# ASCII_Terminal.net
KiCad netlist of a schematic drawn in Altium Designer
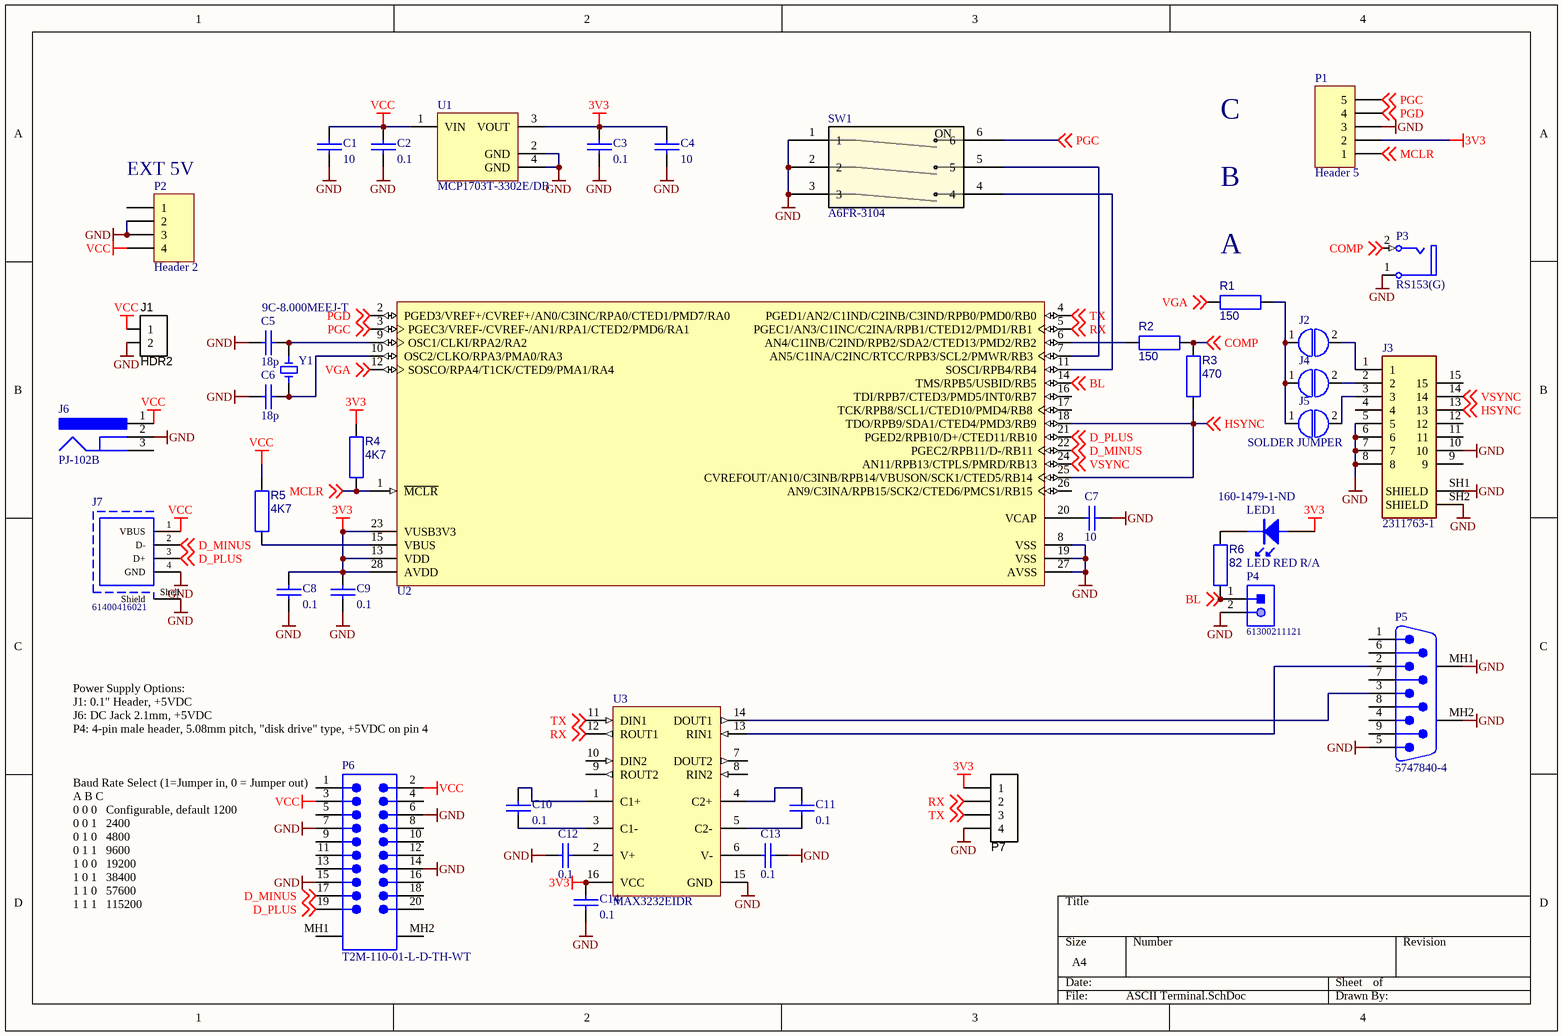
[diagram p0: ASCII Terminal.SchDoc]

(export (version "E")
  (design (tool "Eeschema 10.0.6"))
  (components
    (comp (ref "C1")
      (value "10")
      (footprint "C0805-S")
      (description "Capacitor")
      (fields (field (name "Comment") "VJ0805V475ZXQTW1BC"))
      (libsource (lib "*") (part "CAP"))
    )
    (comp (ref "C2")
      (value "0.1")
      (footprint "C0805-S")
      (description "Capacitor")
      (fields (field (name "Comment") "VJ0805V475ZXQTW1BC"))
      (libsource (lib "*") (part "CAP"))
    )
    (comp (ref "C3")
      (value "0.1")
      (footprint "C0805-S")
      (description "Capacitor")
      (fields (field (name "Comment") "VJ0805V475ZXQTW1BC"))
      (libsource (lib "*") (part "CAP"))
    )
    (comp (ref "C4")
      (value "10")
      (footprint "C0805-S")
      (description "Capacitor")
      (fields (field (name "Comment") "VJ0805V475ZXQTW1BC"))
      (libsource (lib "*") (part "CAP"))
    )
    (comp (ref "C5")
      (value "18p")
      (footprint "C0805-S")
      (description "Capacitor")
      (libsource (lib "*") (part "CAP"))
    )
    (comp (ref "C6")
      (value "18p")
      (footprint "C0805-S")
      (description "Capacitor")
      (libsource (lib "*") (part "CAP"))
    )
    (comp (ref "C7")
      (value "10")
      (footprint "C0805-S")
      (description "Capacitor")
      (fields (field (name "Comment") "VJ0805V475ZXQTW1BC"))
      (libsource (lib "*") (part "CAP"))
    )
    (comp (ref "C8")
      (value "0.1")
      (footprint "C0805-S")
      (description "Capacitor")
      (fields (field (name "Comment") "VJ0805V475ZXQTW1BC"))
      (libsource (lib "*") (part "CAP"))
    )
    (comp (ref "C9")
      (value "0.1")
      (footprint "C0805-S")
      (description "Capacitor")
      (fields (field (name "Comment") "VJ0805V475ZXQTW1BC"))
      (libsource (lib "*") (part "CAP"))
    )
    (comp (ref "C10")
      (value "0.1")
      (footprint "C0805-S")
      (description "Capacitor")
      (fields (field (name "Comment") "VJ0805V475ZXQTW1BC"))
      (libsource (lib "*") (part "CAP"))
    )
    (comp (ref "C11")
      (value "0.1")
      (footprint "C0805-S")
      (description "Capacitor")
      (fields (field (name "Comment") "VJ0805V475ZXQTW1BC"))
      (libsource (lib "*") (part "CAP"))
    )
    (comp (ref "C12")
      (value "0.1")
      (footprint "C0805-S")
      (description "Capacitor")
      (fields (field (name "Comment") "VJ0805V475ZXQTW1BC"))
      (libsource (lib "*") (part "CAP"))
    )
    (comp (ref "C13")
      (value "0.1")
      (footprint "C0805-S")
      (description "Capacitor")
      (fields (field (name "Comment") "VJ0805V475ZXQTW1BC"))
      (libsource (lib "*") (part "CAP"))
    )
    (comp (ref "C14")
      (value "0.1")
      (footprint "C0805-S")
      (description "Capacitor")
      (fields (field (name "Comment") "VJ0805V475ZXQTW1BC"))
      (libsource (lib "*") (part "CAP"))
    )
    (comp (ref "J1")
      (value "HDR2")
      (footprint "HDR1X2 - KK")
      (description "Header, 2-pin")
      (libsource (lib "PBL - Connectors") (part "Header2P"))
    )
    (comp (ref "J2")
      (value "SOLDER JUMPER")
      (footprint "SOLDER JUMPER")
      (libsource (lib "Kanitti") (part "SOLDER JUMPER"))
    )
    (comp (ref "J3")
      (value "2311763-1")
      (footprint "SnapEDApcb:TE_1-1734530-1")
      (description "15 Position D-Sub, High Density Receptacle, Female Sockets Connector")
      (fields (field (name "MP") "1-1734530-1") (field (name "MF") "TE Connectivity"))
      (libsource (lib "SnapEDAsch") (part "2311763-2"))
    )
    (comp (ref "J4")
      (value "SOLDER JUMPER")
      (footprint "SOLDER JUMPER")
      (libsource (lib "Kanitti") (part "SOLDER JUMPER"))
    )
    (comp (ref "J5")
      (value "SOLDER JUMPER")
      (footprint "SOLDER JUMPER")
      (libsource (lib "Kanitti") (part "SOLDER JUMPER"))
    )
    (comp (ref "J6")
      (value "PJ-102B")
      (footprint "CUI-PJ-102B_V")
      (fields (field (name "MANUFACTURER") "CUIInc."))
      (libsource (lib "Altium Content Vault") (part "JACK-2CD3-RN"))
    )
    (comp (ref "J7")
      (value "61400416021")
      (footprint "61400416021")
      (description "USB 2.0 Type A Receptacle WR-COM, Horizontal, THT")
      (fields (field (name "MANUFACTURER") "Wurth Elektronik") (field (name "PUBLISHER") "WurthElektronik"))
      (libsource (lib "Altium Content Vault") (part "WE-USB-4-1SHLD"))
    )
    (comp (ref "LED1")
      (value "LED RED R/A")
      (footprint "LTST-S270")
      (fields (field (name "SUPPLIER PART NUMBER 1") "160-1479-1-ND"))
      (libsource (lib "Kanitti") (part "LED_SIDE_1_6_1_15"))
    )
    (comp (ref "P1")
      (value "Header 5")
      (footprint "HDR1X5")
      (description "Header, 5-Pin")
      (fields (field (name "PUBLISHER") "Altium Limited"))
      (libsource (lib "Miscellaneous Connectors") (part "Header 5"))
    )
    (comp (ref "P2")
      (value "Header 2")
      (footprint "1745521")
      (description "Header, 4-Pin")
      (fields (field (name "PUBLISHER") "Altium Limited"))
      (libsource (lib "Kanitti") (part "Header 4"))
    )
    (comp (ref "P3")
      (value "RS153(G)")
      (footprint "RCAJ-01X")
      (description "RCA Phono Jack, Right Angle, Thru-Hole, Snap-In")
      (fields (field (name "PUBLISHER") "Altium Limited"))
      (libsource (lib "TRA1404(DIFT2)") (part "RCA"))
    )
    (comp (ref "P4")
      (value "61300211121")
      (footprint "61300211121")
      (description "THT Vertical Pin Header WR-PHD, Pitch 2.54 mm, Single Row, 2 pins")
      (fields (field (name "MANUFACTURER") "Wurth Elektronik") (field (name "PUBLISHER") "WurthElektronik"))
      (libsource (lib "Altium Content Vault") (part "WE-CN-1P-M-R2"))
    )
    (comp (ref "P5")
      (value "5747840-4")
      (footprint "TECO-5747840-4_V")
      (fields (field (name "MANUFACTURER") "TE Connectivity"))
      (libsource (lib "Altium Content Vault") (part "CN-2S-2M-D9"))
    )
    (comp (ref "P6")
      (value "T2M-110-01-L-D-TH-WT")
      (footprint "SMTC-T2M-110-01-X-D-TH-WT")
      (fields (field (name "MANUFACTURER") "Samtec"))
      (libsource (lib "Altium Content Vault") (part "SMTC-T2M-110-01-X-D-WT"))
    )
    (comp (ref "P7")
      (value "Programmer")
      (footprint "HDR1X4_2.54mmp")
      (description "Header 4-pin")
      (libsource (lib "PBL - Connectors") (part "Header4P"))
    )
    (comp (ref "R1")
      (value "150")
      (footprint "RESC2012X70N")
      (description "RESISTOR")
      (libsource (lib "SCH") (part "RES2"))
    )
    (comp (ref "R2")
      (value "150")
      (footprint "RESC2012X70N")
      (description "RESISTOR")
      (libsource (lib "SCH") (part "RES2"))
    )
    (comp (ref "R3")
      (value "470")
      (footprint "RESC2012X70N")
      (description "RESISTOR")
      (libsource (lib "SCH") (part "RES2"))
    )
    (comp (ref "R4")
      (value "4K7")
      (footprint "RESC2012X70N")
      (description "RESISTOR")
      (libsource (lib "SCH") (part "RES2"))
    )
    (comp (ref "R5")
      (value "4K7")
      (footprint "RESC2012X70N")
      (description "RESISTOR")
      (libsource (lib "SCH") (part "RES2"))
    )
    (comp (ref "R6")
      (value "82")
      (footprint "RESC2012X70N")
      (description "RESISTOR")
      (libsource (lib "SCH") (part "RES2"))
    )
    (comp (ref "SW1")
      (value "A6FR-3104")
      (footprint "SW_A6FR-3104_OMR")
      (description "No Description Available")
      (fields (field (name "COPYRIGHT") "Copyright (C) 2018 Accelerated Designs. All rights reserved"))
      (libsource (lib "Kanitti") (part "A6FR-3104"))
    )
    (comp (ref "U1")
      (value "MCP1703T-3302E/DB")
      (footprint "SOT-223-DB3_L")
      (libsource (lib "Altium Content Vault") (part "PM-LINEREG-MCP1703-IL4"))
    )
    (comp (ref "U2")
      (value "PIC32MX250F128B-I/SO")
      (footprint "MCHP-SOIC-SO28_M")
      (fields (field (name "MANUFACTURER") "Microchip"))
      (libsource (lib "Altium Content Vault") (part "MCHP-PIC32MX2X0FXXXB-28"))
    )
    (comp (ref "U3")
      (value "MAX3232EIDR")
      (footprint "D0016A_N")
      (libsource (lib "Altium Content Vault") (part "TI-MAX3232E-SOIC_D-16"))
    )
    (comp (ref "Y1")
      (value "9C-8.000MEEJ-T")
      (footprint "XTAL_9C-8.000MEEJ-T")
      (description "8MHz Â±10ppm Crystal 18pF 80 Ohms HC-49/US")
      (fields (field (name "MF") "TXC CORPORATION"))
      (libsource (lib "SnapEDAsch") (part "9C-8.000MEEJ-T"))
    )
  )
  (nets
    (net (code "1") (name "3V3") (class "Default")
      (node (ref "C14") (pin "1") (pinfunction "1_1") (pintype "passive"))
      (node (ref "C3") (pin "1") (pinfunction "1_1") (pintype "passive"))
      (node (ref "C4") (pin "1") (pinfunction "1_1") (pintype "passive"))
      (node (ref "C8") (pin "1") (pinfunction "1_1") (pintype "passive"))
      (node (ref "C9") (pin "1") (pinfunction "1_1") (pintype "passive"))
      (node (ref "LED1") (pin "A") (pinfunction "A_A") (pintype "passive"))
      (node (ref "P1") (pin "2") (pinfunction "2_2") (pintype "passive"))
      (node (ref "P7") (pin "1") (pinfunction "1_1") (pintype "passive"))
      (node (ref "R4") (pin "2") (pintype "passive"))
      (node (ref "U1") (pin "3") (pinfunction "VOUT_3") (pintype "power_in"))
      (node (ref "U2") (pin "13") (pinfunction "VDD_13") (pintype "power_in"))
      (node (ref "U2") (pin "23") (pinfunction "VUSB3V3_23") (pintype "power_in"))
      (node (ref "U2") (pin "28") (pinfunction "AVDD_28") (pintype "power_in"))
      (node (ref "U3") (pin "16") (pinfunction "VCC_16") (pintype "power_in"))
    )
    (net (code "2") (name "BL") (class "Default")
      (node (ref "P4") (pin "1") (pinfunction "1_1") (pintype "passive"))
      (node (ref "R6") (pin "2") (pintype "passive"))
      (node (ref "U2") (pin "14") (pinfunction "TMS/RPB5/USBID/RB5_14") (pintype "bidirectional"))
    )
    (net (code "3") (name "COMP") (class "Default")
      (node (ref "P3") (pin "2") (pinfunction "Signal_2") (pintype "input"))
      (node (ref "R2") (pin "1") (pintype "passive"))
      (node (ref "R3") (pin "1") (pintype "passive"))
    )
    (net (code "4") (name "D_MINUS") (class "Default")
      (node (ref "J7") (pin "2") (pinfunction "D-_2") (pintype "passive"))
      (node (ref "P6") (pin "17") (pinfunction "17_17") (pintype "passive"))
      (node (ref "U2") (pin "22") (pinfunction "PGEC2/RPB11/D-/RB11_22") (pintype "bidirectional"))
    )
    (net (code "5") (name "D_PLUS") (class "Default")
      (node (ref "J7") (pin "3") (pinfunction "D+_3") (pintype "passive"))
      (node (ref "P6") (pin "19") (pinfunction "19_19") (pintype "passive"))
      (node (ref "U2") (pin "21") (pinfunction "PGED2/RPB10/D+/CTED11/RB10_21") (pintype "bidirectional"))
    )
    (net (code "6") (name "GND") (class "Default")
      (node (ref "C1") (pin "2") (pinfunction "2_2") (pintype "passive"))
      (node (ref "C12") (pin "1") (pinfunction "1_1") (pintype "passive"))
      (node (ref "C13") (pin "2") (pinfunction "2_2") (pintype "passive"))
      (node (ref "C14") (pin "2") (pinfunction "2_2") (pintype "passive"))
      (node (ref "C2") (pin "2") (pinfunction "2_2") (pintype "passive"))
      (node (ref "C3") (pin "2") (pinfunction "2_2") (pintype "passive"))
      (node (ref "C4") (pin "2") (pinfunction "2_2") (pintype "passive"))
      (node (ref "C5") (pin "1") (pinfunction "1_1") (pintype "passive"))
      (node (ref "C6") (pin "1") (pinfunction "1_1") (pintype "passive"))
      (node (ref "C7") (pin "2") (pinfunction "2_2") (pintype "passive"))
      (node (ref "C8") (pin "2") (pinfunction "2_2") (pintype "passive"))
      (node (ref "C9") (pin "2") (pinfunction "2_2") (pintype "passive"))
      (node (ref "J1") (pin "2") (pinfunction "2_2") (pintype "passive"))
      (node (ref "J3") (pin "10") (pinfunction "10_10") (pintype "passive"))
      (node (ref "J3") (pin "5") (pinfunction "5_5") (pintype "passive"))
      (node (ref "J3") (pin "6") (pinfunction "6_6") (pintype "passive"))
      (node (ref "J3") (pin "7") (pinfunction "7_7") (pintype "passive"))
      (node (ref "J3") (pin "8") (pinfunction "8_8") (pintype "passive"))
      (node (ref "J3") (pin "SH1") (pinfunction "SHIELD_SH1") (pintype "passive"))
      (node (ref "J3") (pin "SH2") (pinfunction "SHIELD_SH2") (pintype "passive"))
      (node (ref "J6") (pin "2") (pinfunction "2_2") (pintype "passive"))
      (node (ref "J7") (pin "4") (pinfunction "GND_4") (pintype "passive"))
      (node (ref "J7") (pin "Shell") (pinfunction "Shield_Shell") (pintype "passive"))
      (node (ref "P1") (pin "3") (pinfunction "3_3") (pintype "passive"))
      (node (ref "P2") (pin "2") (pinfunction "2_2") (pintype "passive"))
      (node (ref "P2") (pin "3") (pinfunction "3_3") (pintype "passive"))
      (node (ref "P3") (pin "1") (pinfunction "Ground_1") (pintype "power_in"))
      (node (ref "P4") (pin "2") (pinfunction "2_2") (pintype "passive"))
      (node (ref "P5") (pin "5") (pinfunction "5_5") (pintype "passive"))
      (node (ref "P5") (pin "MH1") (pinfunction "MH1_MH1") (pintype "passive"))
      (node (ref "P5") (pin "MH2") (pinfunction "MH2_MH2") (pintype "passive"))
      (node (ref "P6") (pin "14") (pinfunction "14_14") (pintype "passive"))
      (node (ref "P6") (pin "15") (pinfunction "15_15") (pintype "passive"))
      (node (ref "P6") (pin "6") (pinfunction "6_6") (pintype "passive"))
      (node (ref "P6") (pin "7") (pinfunction "7_7") (pintype "passive"))
      (node (ref "P7") (pin "4") (pinfunction "4_4") (pintype "passive"))
      (node (ref "SW1") (pin "1") (pinfunction "1_1") (pintype "passive"))
      (node (ref "SW1") (pin "2") (pinfunction "2_2") (pintype "passive"))
      (node (ref "SW1") (pin "3") (pinfunction "3_3") (pintype "passive"))
      (node (ref "U1") (pin "2") (pinfunction "GND_2") (pintype "power_in"))
      (node (ref "U1") (pin "4") (pinfunction "GND_4") (pintype "power_in"))
      (node (ref "U2") (pin "19") (pinfunction "VSS_19") (pintype "power_in"))
      (node (ref "U2") (pin "27") (pinfunction "AVSS_27") (pintype "power_in"))
      (node (ref "U2") (pin "8") (pinfunction "VSS_8") (pintype "power_in"))
      (node (ref "U3") (pin "15") (pinfunction "GND_15") (pintype "power_in"))
    )
    (net (code "7") (name "HSYNC") (class "Default")
      (node (ref "J3") (pin "13") (pinfunction "13_13") (pintype "passive"))
      (node (ref "R3") (pin "2") (pintype "passive"))
      (node (ref "U2") (pin "18") (pinfunction "TDO/RPB9/SDA1/CTED4/PMD3/RB9_18") (pintype "bidirectional"))
      (node (ref "U2") (pin "25") (pinfunction "CVREFOUT/AN10/C3INB/RPB14/VBUSON/SCK1/CTED5/RB14_25") (pintype "bidirectional"))
    )
    (net (code "8") (name "MCLR") (class "Default")
      (node (ref "P1") (pin "1") (pinfunction "1_1") (pintype "passive"))
      (node (ref "R4") (pin "1") (pintype "passive"))
      (node (ref "U2") (pin "1") (pinfunction "~{MCLR}_1") (pintype "input"))
    )
    (net (code "9") (name "Net-(J2-7)") (class "Default")
      (node (ref "J2") (pin "1") (pinfunction "7_1") (pintype "passive"))
      (node (ref "J4") (pin "1") (pinfunction "7_1") (pintype "passive"))
      (node (ref "J5") (pin "1") (pinfunction "7_1") (pintype "passive"))
      (node (ref "R1") (pin "1") (pintype "passive"))
    )
    (net (code "10") (name "Net-(J2-Pad2)") (class "Default")
      (node (ref "J2") (pin "2") (pinfunction "2_2") (pintype "passive"))
      (node (ref "J3") (pin "1") (pinfunction "1_1") (pintype "passive"))
    )
    (net (code "11") (name "Net-(J3-Pad2)") (class "Default")
      (node (ref "J3") (pin "2") (pinfunction "2_2") (pintype "passive"))
      (node (ref "J4") (pin "2") (pinfunction "2_2") (pintype "passive"))
    )
    (net (code "12") (name "Net-(J3-Pad3)") (class "Default")
      (node (ref "J3") (pin "3") (pinfunction "3_3") (pintype "passive"))
      (node (ref "J5") (pin "2") (pinfunction "2_2") (pintype "passive"))
    )
    (net (code "13") (name "Net-(LED1-PadK)") (class "Default")
      (node (ref "LED1") (pin "K") (pinfunction "K_K") (pintype "passive"))
      (node (ref "R6") (pin "1") (pintype "passive"))
    )
    (net (code "14") (name "Net-(U2-AN4{slash}C1INB{slash}C2IND{slash}RPB2{slash}SDA2{slash}CTED13{slash}PMD2{slash}RB2)") (class "Default")
      (node (ref "R2") (pin "2") (pintype "passive"))
      (node (ref "U2") (pin "6") (pinfunction "AN4/C1INB/C2IND/RPB2/SDA2/CTED13/PMD2/RB2_6") (pintype "bidirectional"))
    )
    (net (code "15") (name "Net-(U2-AN5{slash}C1INA{slash}C2INC{slash}RTCC{slash}RPB3{slash}SCL2{slash}PMWR{slash}RB3)") (class "Default")
      (node (ref "SW1") (pin "5") (pinfunction "5_5") (pintype "passive"))
      (node (ref "U2") (pin "7") (pinfunction "AN5/C1INA/C2INC/RTCC/RPB3/SCL2/PMWR/RB3_7") (pintype "bidirectional"))
    )
    (net (code "16") (name "Net-(U2-OSC1{slash}CLKI{slash}RPA2{slash}RA2)") (class "Default")
      (node (ref "C5") (pin "2") (pinfunction "2_2") (pintype "passive"))
      (node (ref "U2") (pin "9") (pinfunction "OSC1/CLKI/RPA2/RA2_9") (pintype "bidirectional"))
      (node (ref "Y1") (pin "2") (pinfunction "2_2") (pintype "passive"))
    )
    (net (code "17") (name "Net-(U2-OSC2{slash}CLKO{slash}RPA3{slash}PMA0{slash}RA3)") (class "Default")
      (node (ref "C6") (pin "2") (pinfunction "2_2") (pintype "passive"))
      (node (ref "U2") (pin "10") (pinfunction "OSC2/CLKO/RPA3/PMA0/RA3_10") (pintype "bidirectional"))
      (node (ref "Y1") (pin "1") (pinfunction "1_1") (pintype "passive"))
    )
    (net (code "18") (name "Net-(U2-SOSCI{slash}RPB4{slash}RB4)") (class "Default")
      (node (ref "SW1") (pin "4") (pinfunction "4_4") (pintype "passive"))
      (node (ref "U2") (pin "11") (pinfunction "SOSCI/RPB4/RB4_11") (pintype "bidirectional"))
    )
    (net (code "19") (name "Net-(U2-VBUS)") (class "Default")
      (node (ref "R5") (pin "1") (pintype "passive"))
      (node (ref "U2") (pin "15") (pinfunction "VBUS_15") (pintype "power_in"))
    )
    (net (code "20") (name "Net-(U2-VCAP)") (class "Default")
      (node (ref "C7") (pin "1") (pinfunction "1_1") (pintype "passive"))
      (node (ref "U2") (pin "20") (pinfunction "VCAP_20") (pintype "passive"))
    )
    (net (code "21") (name "Net-(U3-C1+)") (class "Default")
      (node (ref "C10") (pin "1") (pinfunction "1_1") (pintype "passive"))
      (node (ref "U3") (pin "1") (pinfunction "C1+_1") (pintype "passive"))
    )
    (net (code "22") (name "Net-(U3-C1-)") (class "Default")
      (node (ref "C10") (pin "2") (pinfunction "2_2") (pintype "passive"))
      (node (ref "U3") (pin "3") (pinfunction "C1-_3") (pintype "passive"))
    )
    (net (code "23") (name "Net-(U3-C2+)") (class "Default")
      (node (ref "C11") (pin "1") (pinfunction "1_1") (pintype "passive"))
      (node (ref "U3") (pin "4") (pinfunction "C2+_4") (pintype "passive"))
    )
    (net (code "24") (name "Net-(U3-C2-)") (class "Default")
      (node (ref "C11") (pin "2") (pinfunction "2_2") (pintype "passive"))
      (node (ref "U3") (pin "5") (pinfunction "C2-_5") (pintype "passive"))
    )
    (net (code "25") (name "Net-(U3-DOUT1)") (class "Default")
      (node (ref "P5") (pin "3") (pinfunction "3_3") (pintype "passive"))
      (node (ref "U3") (pin "14") (pinfunction "DOUT1_14") (pintype "output"))
    )
    (net (code "26") (name "Net-(U3-RIN1)") (class "Default")
      (node (ref "P5") (pin "2") (pinfunction "2_2") (pintype "passive"))
      (node (ref "U3") (pin "13") (pinfunction "RIN1_13") (pintype "input"))
    )
    (net (code "27") (name "Net-(U3-V+)") (class "Default")
      (node (ref "C12") (pin "2") (pinfunction "2_2") (pintype "passive"))
      (node (ref "U3") (pin "2") (pinfunction "V+_2") (pintype "power_in"))
    )
    (net (code "28") (name "Net-(U3-V-)") (class "Default")
      (node (ref "C13") (pin "1") (pinfunction "1_1") (pintype "passive"))
      (node (ref "U3") (pin "6") (pinfunction "V-_6") (pintype "power_in"))
    )
    (net (code "29") (name "PGC") (class "Default")
      (node (ref "P1") (pin "5") (pinfunction "5_5") (pintype "passive"))
      (node (ref "SW1") (pin "6") (pinfunction "6_6") (pintype "passive"))
      (node (ref "U2") (pin "3") (pinfunction "PGEC3/VREF-/CVREF-/AN1/RPA1/CTED2/PMD6/RA1_3") (pintype "bidirectional"))
    )
    (net (code "30") (name "PGD") (class "Default")
      (node (ref "P1") (pin "4") (pinfunction "4_4") (pintype "passive"))
      (node (ref "U2") (pin "2") (pinfunction "PGED3/VREF+/CVREF+/AN0/C3INC/RPA0/CTED1/PMD7/RA0_2") (pintype "bidirectional"))
    )
    (net (code "31") (name "RX") (class "Default")
      (node (ref "P7") (pin "2") (pinfunction "2_2") (pintype "passive"))
      (node (ref "U2") (pin "5") (pinfunction "PGEC1/AN3/C1INC/C2INA/RPB1/CTED12/PMD1/RB1_5") (pintype "bidirectional"))
      (node (ref "U3") (pin "12") (pinfunction "ROUT1_12") (pintype "output"))
    )
    (net (code "32") (name "TX") (class "Default")
      (node (ref "P7") (pin "3") (pinfunction "3_3") (pintype "passive"))
      (node (ref "U2") (pin "4") (pinfunction "PGED1/AN2/C1IND/C2INB/C3IND/RPB0/PMD0/RB0_4") (pintype "bidirectional"))
      (node (ref "U3") (pin "11") (pinfunction "DIN1_11") (pintype "input"))
    )
    (net (code "33") (name "VCC") (class "Default")
      (node (ref "C1") (pin "1") (pinfunction "1_1") (pintype "passive"))
      (node (ref "C2") (pin "1") (pinfunction "1_1") (pintype "passive"))
      (node (ref "J1") (pin "1") (pinfunction "1_1") (pintype "passive"))
      (node (ref "J6") (pin "1") (pinfunction "1_1") (pintype "passive"))
      (node (ref "J7") (pin "1") (pinfunction "VBUS_1") (pintype "passive"))
      (node (ref "P2") (pin "4") (pinfunction "4_4") (pintype "passive"))
      (node (ref "P6") (pin "2") (pinfunction "2_2") (pintype "passive"))
      (node (ref "P6") (pin "3") (pinfunction "3_3") (pintype "passive"))
      (node (ref "R5") (pin "2") (pintype "passive"))
      (node (ref "U1") (pin "1") (pinfunction "VIN_1") (pintype "power_in"))
    )
    (net (code "34") (name "VGA") (class "Default")
      (node (ref "R1") (pin "2") (pintype "passive"))
      (node (ref "U2") (pin "12") (pinfunction "SOSCO/RPA4/T1CK/CTED9/PMA1/RA4_12") (pintype "bidirectional"))
    )
    (net (code "35") (name "VSYNC") (class "Default")
      (node (ref "J3") (pin "14") (pinfunction "14_14") (pintype "passive"))
      (node (ref "U2") (pin "24") (pinfunction "AN11/RPB13/CTPLS/PMRD/RB13_24") (pintype "bidirectional"))
    )
    (net (code "36") (name "unconnected-(J3-Pad4)") (class "Default")
      (node (ref "J3") (pin "4") (pinfunction "4_4") (pintype "passive"))
    )
    (net (code "37") (name "unconnected-(J3-Pad9)") (class "Default")
      (node (ref "J3") (pin "9") (pinfunction "9_9") (pintype "passive"))
    )
    (net (code "38") (name "unconnected-(J3-Pad11)") (class "Default")
      (node (ref "J3") (pin "11") (pinfunction "11_11") (pintype "passive"))
    )
    (net (code "39") (name "unconnected-(J3-Pad12)") (class "Default")
      (node (ref "J3") (pin "12") (pinfunction "12_12") (pintype "passive"))
    )
    (net (code "40") (name "unconnected-(J3-Pad15)") (class "Default")
      (node (ref "J3") (pin "15") (pinfunction "15_15") (pintype "passive"))
    )
    (net (code "41") (name "unconnected-(J6-Pad3)") (class "Default")
      (node (ref "J6") (pin "3") (pinfunction "3_3") (pintype "passive"))
    )
    (net (code "42") (name "unconnected-(P2-Pad1)") (class "Default")
      (node (ref "P2") (pin "1") (pinfunction "1_1") (pintype "passive"))
    )
    (net (code "43") (name "unconnected-(P5-Pad1)") (class "Default")
      (node (ref "P5") (pin "1") (pinfunction "1_1") (pintype "passive"))
    )
    (net (code "44") (name "unconnected-(P5-Pad4)") (class "Default")
      (node (ref "P5") (pin "4") (pinfunction "4_4") (pintype "passive"))
    )
    (net (code "45") (name "unconnected-(P5-Pad6)") (class "Default")
      (node (ref "P5") (pin "6") (pinfunction "6_6") (pintype "passive"))
    )
    (net (code "46") (name "unconnected-(P5-Pad7)") (class "Default")
      (node (ref "P5") (pin "7") (pinfunction "7_7") (pintype "passive"))
    )
    (net (code "47") (name "unconnected-(P5-Pad8)") (class "Default")
      (node (ref "P5") (pin "8") (pinfunction "8_8") (pintype "passive"))
    )
    (net (code "48") (name "unconnected-(P5-Pad9)") (class "Default")
      (node (ref "P5") (pin "9") (pinfunction "9_9") (pintype "passive"))
    )
    (net (code "49") (name "unconnected-(P6-Pad1)") (class "Default")
      (node (ref "P6") (pin "1") (pinfunction "1_1") (pintype "passive"))
    )
    (net (code "50") (name "unconnected-(P6-Pad4)") (class "Default")
      (node (ref "P6") (pin "4") (pinfunction "4_4") (pintype "passive"))
    )
    (net (code "51") (name "unconnected-(P6-Pad5)") (class "Default")
      (node (ref "P6") (pin "5") (pinfunction "5_5") (pintype "passive"))
    )
    (net (code "52") (name "unconnected-(P6-Pad8)") (class "Default")
      (node (ref "P6") (pin "8") (pinfunction "8_8") (pintype "passive"))
    )
    (net (code "53") (name "unconnected-(P6-Pad9)") (class "Default")
      (node (ref "P6") (pin "9") (pinfunction "9_9") (pintype "passive"))
    )
    (net (code "54") (name "unconnected-(P6-Pad10)") (class "Default")
      (node (ref "P6") (pin "10") (pinfunction "10_10") (pintype "passive"))
    )
    (net (code "55") (name "unconnected-(P6-Pad11)") (class "Default")
      (node (ref "P6") (pin "11") (pinfunction "11_11") (pintype "passive"))
    )
    (net (code "56") (name "unconnected-(P6-Pad12)") (class "Default")
      (node (ref "P6") (pin "12") (pinfunction "12_12") (pintype "passive"))
    )
    (net (code "57") (name "unconnected-(P6-Pad13)") (class "Default")
      (node (ref "P6") (pin "13") (pinfunction "13_13") (pintype "passive"))
    )
    (net (code "58") (name "unconnected-(P6-Pad16)") (class "Default")
      (node (ref "P6") (pin "16") (pinfunction "16_16") (pintype "passive"))
    )
    (net (code "59") (name "unconnected-(P6-Pad18)") (class "Default")
      (node (ref "P6") (pin "18") (pinfunction "18_18") (pintype "passive"))
    )
    (net (code "60") (name "unconnected-(P6-Pad20)") (class "Default")
      (node (ref "P6") (pin "20") (pinfunction "20_20") (pintype "passive"))
    )
    (net (code "61") (name "unconnected-(P6-PadMH1)") (class "Default")
      (node (ref "P6") (pin "MH1") (pinfunction "MH1_MH1") (pintype "passive"))
    )
    (net (code "62") (name "unconnected-(P6-PadMH2)") (class "Default")
      (node (ref "P6") (pin "MH2") (pinfunction "MH2_MH2") (pintype "passive"))
    )
    (net (code "63") (name "unconnected-(U2-AN9{slash}C3INA{slash}RPB15{slash}SCK2{slash}CTED6{slash}PMCS1{slash}RB15-Pad26)") (class "Default")
      (node (ref "U2") (pin "26") (pinfunction "AN9/C3INA/RPB15/SCK2/CTED6/PMCS1/RB15_26") (pintype "bidirectional"))
    )
    (net (code "64") (name "unconnected-(U2-TCK{slash}RPB8{slash}SCL1{slash}CTED10{slash}PMD4{slash}RB8-Pad17)") (class "Default")
      (node (ref "U2") (pin "17") (pinfunction "TCK/RPB8/SCL1/CTED10/PMD4/RB8_17") (pintype "bidirectional"))
    )
    (net (code "65") (name "unconnected-(U2-TDI{slash}RPB7{slash}CTED3{slash}PMD5{slash}INT0{slash}RB7-Pad16)") (class "Default")
      (node (ref "U2") (pin "16") (pinfunction "TDI/RPB7/CTED3/PMD5/INT0/RB7_16") (pintype "bidirectional"))
    )
    (net (code "66") (name "unconnected-(U3-DIN2-Pad10)") (class "Default")
      (node (ref "U3") (pin "10") (pinfunction "DIN2_10") (pintype "input"))
    )
    (net (code "67") (name "unconnected-(U3-DOUT2-Pad7)") (class "Default")
      (node (ref "U3") (pin "7") (pinfunction "DOUT2_7") (pintype "output"))
    )
    (net (code "68") (name "unconnected-(U3-RIN2-Pad8)") (class "Default")
      (node (ref "U3") (pin "8") (pinfunction "RIN2_8") (pintype "input"))
    )
    (net (code "69") (name "unconnected-(U3-ROUT2-Pad9)") (class "Default")
      (node (ref "U3") (pin "9") (pinfunction "ROUT2_9") (pintype "output"))
    )
  )
)
